# pena.net
KiCad netlist of a schematic drawn in EAGLE
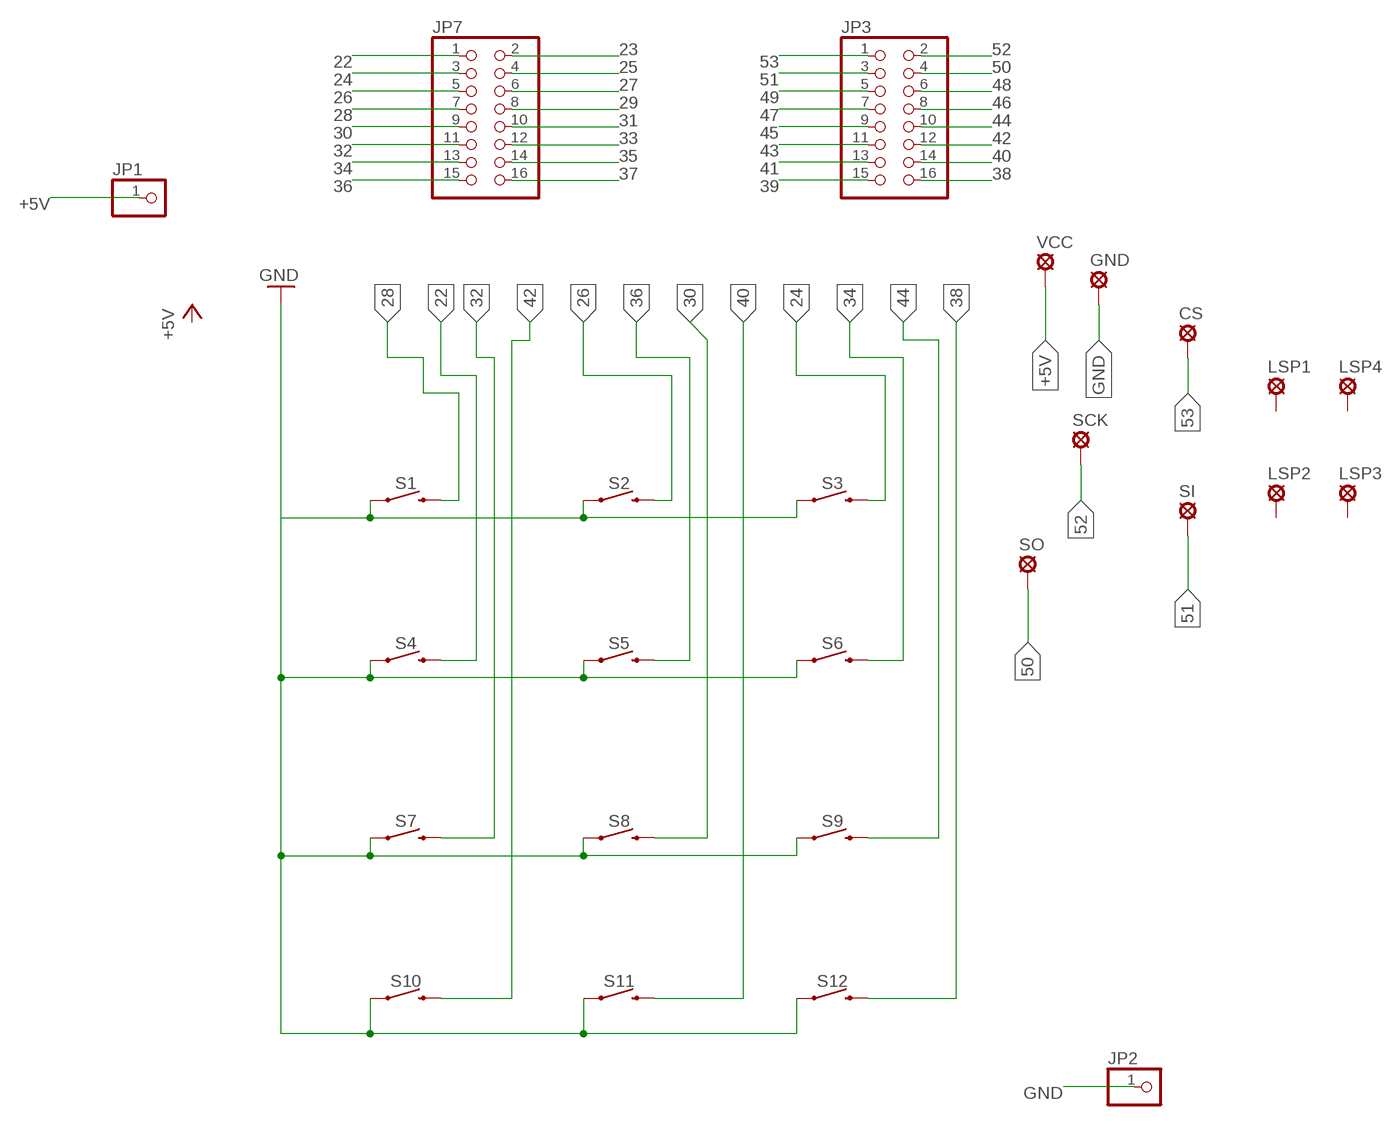
[diagram p0: schematic, sheet 1]

(export (version "E")
  (design (tool "Eeschema 10.0.6"))
  (components
    (comp (ref "CS")
      (value "SE11")
      (footprint "eagle-import:SE11")
      (libsource (lib "eagle-import") (part "SE11"))
    )
    (comp (ref "GND")
      (value "SE11")
      (footprint "eagle-import:SE11")
      (libsource (lib "eagle-import") (part "SE11"))
    )
    (comp (ref "JP1")
      (value "PINHD-1X1")
      (footprint "eagle-import:1X01")
      (libsource (lib "eagle-import") (part "PINHD-1X1"))
    )
    (comp (ref "JP2")
      (value "PINHD-1X1")
      (footprint "eagle-import:1X01")
      (libsource (lib "eagle-import") (part "PINHD-1X1"))
    )
    (comp (ref "JP3")
      (value "PINHD-2X8")
      (footprint "eagle-import:2X08")
      (libsource (lib "eagle-import") (part "PINHD-2X8"))
    )
    (comp (ref "JP7")
      (value "PINHD-2X8")
      (footprint "eagle-import:2X08")
      (libsource (lib "eagle-import") (part "PINHD-2X8"))
    )
    (comp (ref "LSP1")
      (value "SE11")
      (footprint "eagle-import:SE11")
      (libsource (lib "eagle-import") (part "SE11"))
    )
    (comp (ref "LSP2")
      (value "SE11")
      (footprint "eagle-import:SE11")
      (libsource (lib "eagle-import") (part "SE11"))
    )
    (comp (ref "LSP3")
      (value "SE11")
      (footprint "eagle-import:SE11")
      (libsource (lib "eagle-import") (part "SE11"))
    )
    (comp (ref "LSP4")
      (value "SE11")
      (footprint "eagle-import:SE11")
      (libsource (lib "eagle-import") (part "SE11"))
    )
    (comp (ref "S1")
      (value "MOMENTARY-SWITCH-SPST-PTH-12MM")
      (footprint "eagle-import:TACTILE_SWITCH_PTH_12MM")
      (libsource (lib "eagle-import") (part "MOMENTARY-SWITCH-SPST-PTH-12MM"))
    )
    (comp (ref "S2")
      (value "MOMENTARY-SWITCH-SPST-PTH-12MM")
      (footprint "eagle-import:TACTILE_SWITCH_PTH_12MM")
      (libsource (lib "eagle-import") (part "MOMENTARY-SWITCH-SPST-PTH-12MM"))
    )
    (comp (ref "S3")
      (value "MOMENTARY-SWITCH-SPST-PTH-12MM")
      (footprint "eagle-import:TACTILE_SWITCH_PTH_12MM")
      (libsource (lib "eagle-import") (part "MOMENTARY-SWITCH-SPST-PTH-12MM"))
    )
    (comp (ref "S4")
      (value "MOMENTARY-SWITCH-SPST-PTH-12MM")
      (footprint "eagle-import:TACTILE_SWITCH_PTH_12MM")
      (libsource (lib "eagle-import") (part "MOMENTARY-SWITCH-SPST-PTH-12MM"))
    )
    (comp (ref "S5")
      (value "MOMENTARY-SWITCH-SPST-PTH-12MM")
      (footprint "eagle-import:TACTILE_SWITCH_PTH_12MM")
      (libsource (lib "eagle-import") (part "MOMENTARY-SWITCH-SPST-PTH-12MM"))
    )
    (comp (ref "S6")
      (value "MOMENTARY-SWITCH-SPST-PTH-12MM")
      (footprint "eagle-import:TACTILE_SWITCH_PTH_12MM")
      (libsource (lib "eagle-import") (part "MOMENTARY-SWITCH-SPST-PTH-12MM"))
    )
    (comp (ref "S7")
      (value "MOMENTARY-SWITCH-SPST-PTH-12MM")
      (footprint "eagle-import:TACTILE_SWITCH_PTH_12MM")
      (libsource (lib "eagle-import") (part "MOMENTARY-SWITCH-SPST-PTH-12MM"))
    )
    (comp (ref "S8")
      (value "MOMENTARY-SWITCH-SPST-PTH-12MM")
      (footprint "eagle-import:TACTILE_SWITCH_PTH_12MM")
      (libsource (lib "eagle-import") (part "MOMENTARY-SWITCH-SPST-PTH-12MM"))
    )
    (comp (ref "S9")
      (value "MOMENTARY-SWITCH-SPST-PTH-12MM")
      (footprint "eagle-import:TACTILE_SWITCH_PTH_12MM")
      (libsource (lib "eagle-import") (part "MOMENTARY-SWITCH-SPST-PTH-12MM"))
    )
    (comp (ref "S10")
      (value "MOMENTARY-SWITCH-SPST-PTH-12MM")
      (footprint "eagle-import:TACTILE_SWITCH_PTH_12MM")
      (libsource (lib "eagle-import") (part "MOMENTARY-SWITCH-SPST-PTH-12MM"))
    )
    (comp (ref "S11")
      (value "MOMENTARY-SWITCH-SPST-PTH-12MM")
      (footprint "eagle-import:TACTILE_SWITCH_PTH_12MM")
      (libsource (lib "eagle-import") (part "MOMENTARY-SWITCH-SPST-PTH-12MM"))
    )
    (comp (ref "S12")
      (value "MOMENTARY-SWITCH-SPST-PTH-12MM")
      (footprint "eagle-import:TACTILE_SWITCH_PTH_12MM")
      (libsource (lib "eagle-import") (part "MOMENTARY-SWITCH-SPST-PTH-12MM"))
    )
    (comp (ref "SCK")
      (value "SE11")
      (footprint "eagle-import:SE11")
      (libsource (lib "eagle-import") (part "SE11"))
    )
    (comp (ref "SI")
      (value "SE11")
      (footprint "eagle-import:SE11")
      (libsource (lib "eagle-import") (part "SE11"))
    )
    (comp (ref "SO")
      (value "SE11")
      (footprint "eagle-import:SE11")
      (libsource (lib "eagle-import") (part "SE11"))
    )
    (comp (ref "VCC")
      (value "SE11")
      (footprint "eagle-import:SE11")
      (libsource (lib "eagle-import") (part "SE11"))
    )
  )
  (nets
    (net (code "1") (name "+5V") (class "Default")
      (node (ref "JP1") (pin "1") (pinfunction "1_1") (pintype "passive"))
      (node (ref "VCC") (pin "MP") (pinfunction "MP_MP") (pintype "passive"))
    )
    (net (code "2") (name "/23") (class "Default")
      (node (ref "JP7") (pin "2") (pinfunction "2_2") (pintype "passive"))
    )
    (net (code "3") (name "/25") (class "Default")
      (node (ref "JP7") (pin "4") (pinfunction "4_4") (pintype "passive"))
    )
    (net (code "4") (name "/27") (class "Default")
      (node (ref "JP7") (pin "6") (pinfunction "6_6") (pintype "passive"))
    )
    (net (code "5") (name "/29") (class "Default")
      (node (ref "JP7") (pin "8") (pinfunction "8_8") (pintype "passive"))
    )
    (net (code "6") (name "/31") (class "Default")
      (node (ref "JP7") (pin "10") (pinfunction "10_10") (pintype "passive"))
    )
    (net (code "7") (name "/33") (class "Default")
      (node (ref "JP7") (pin "12") (pinfunction "12_12") (pintype "passive"))
    )
    (net (code "8") (name "/35") (class "Default")
      (node (ref "JP7") (pin "14") (pinfunction "14_14") (pintype "passive"))
    )
    (net (code "9") (name "/37") (class "Default")
      (node (ref "JP7") (pin "16") (pinfunction "16_16") (pintype "passive"))
    )
    (net (code "10") (name "/39") (class "Default")
      (node (ref "JP3") (pin "15") (pinfunction "15_15") (pintype "passive"))
    )
    (net (code "11") (name "/41") (class "Default")
      (node (ref "JP3") (pin "13") (pinfunction "13_13") (pintype "passive"))
    )
    (net (code "12") (name "/43") (class "Default")
      (node (ref "JP3") (pin "11") (pinfunction "11_11") (pintype "passive"))
    )
    (net (code "13") (name "/45") (class "Default")
      (node (ref "JP3") (pin "9") (pinfunction "9_9") (pintype "passive"))
    )
    (net (code "14") (name "/46") (class "Default")
      (node (ref "JP3") (pin "8") (pinfunction "8_8") (pintype "passive"))
    )
    (net (code "15") (name "/47") (class "Default")
      (node (ref "JP3") (pin "7") (pinfunction "7_7") (pintype "passive"))
    )
    (net (code "16") (name "/48") (class "Default")
      (node (ref "JP3") (pin "6") (pinfunction "6_6") (pintype "passive"))
    )
    (net (code "17") (name "/49") (class "Default")
      (node (ref "JP3") (pin "5") (pinfunction "5_5") (pintype "passive"))
    )
    (net (code "18") (name "22") (class "Default")
      (node (ref "JP7") (pin "1") (pinfunction "1_1") (pintype "passive"))
      (node (ref "S4") (pin "3") (pinfunction "2_3") (pintype "passive"))
    )
    (net (code "19") (name "24") (class "Default")
      (node (ref "JP7") (pin "3") (pinfunction "3_3") (pintype "passive"))
      (node (ref "S3") (pin "3") (pinfunction "2_3") (pintype "passive"))
    )
    (net (code "20") (name "26") (class "Default")
      (node (ref "JP7") (pin "5") (pinfunction "5_5") (pintype "passive"))
      (node (ref "S2") (pin "3") (pinfunction "2_3") (pintype "passive"))
    )
    (net (code "21") (name "28") (class "Default")
      (node (ref "JP7") (pin "7") (pinfunction "7_7") (pintype "passive"))
      (node (ref "S1") (pin "3") (pinfunction "2_3") (pintype "passive"))
    )
    (net (code "22") (name "30") (class "Default")
      (node (ref "JP7") (pin "9") (pinfunction "9_9") (pintype "passive"))
      (node (ref "S8") (pin "3") (pinfunction "2_3") (pintype "passive"))
    )
    (net (code "23") (name "32") (class "Default")
      (node (ref "JP7") (pin "11") (pinfunction "11_11") (pintype "passive"))
      (node (ref "S7") (pin "3") (pinfunction "2_3") (pintype "passive"))
    )
    (net (code "24") (name "34") (class "Default")
      (node (ref "JP7") (pin "13") (pinfunction "13_13") (pintype "passive"))
      (node (ref "S6") (pin "3") (pinfunction "2_3") (pintype "passive"))
    )
    (net (code "25") (name "36") (class "Default")
      (node (ref "JP7") (pin "15") (pinfunction "15_15") (pintype "passive"))
      (node (ref "S5") (pin "3") (pinfunction "2_3") (pintype "passive"))
    )
    (net (code "26") (name "38") (class "Default")
      (node (ref "JP3") (pin "16") (pinfunction "16_16") (pintype "passive"))
      (node (ref "S12") (pin "3") (pinfunction "2_3") (pintype "passive"))
    )
    (net (code "27") (name "40") (class "Default")
      (node (ref "JP3") (pin "14") (pinfunction "14_14") (pintype "passive"))
      (node (ref "S11") (pin "3") (pinfunction "2_3") (pintype "passive"))
    )
    (net (code "28") (name "42") (class "Default")
      (node (ref "JP3") (pin "12") (pinfunction "12_12") (pintype "passive"))
      (node (ref "S10") (pin "3") (pinfunction "2_3") (pintype "passive"))
    )
    (net (code "29") (name "44") (class "Default")
      (node (ref "JP3") (pin "10") (pinfunction "10_10") (pintype "passive"))
      (node (ref "S9") (pin "3") (pinfunction "2_3") (pintype "passive"))
    )
    (net (code "30") (name "50") (class "Default")
      (node (ref "JP3") (pin "4") (pinfunction "4_4") (pintype "passive"))
      (node (ref "SO") (pin "MP") (pinfunction "MP_MP") (pintype "passive"))
    )
    (net (code "31") (name "51") (class "Default")
      (node (ref "JP3") (pin "3") (pinfunction "3_3") (pintype "passive"))
      (node (ref "SI") (pin "MP") (pinfunction "MP_MP") (pintype "passive"))
    )
    (net (code "32") (name "52") (class "Default")
      (node (ref "JP3") (pin "2") (pinfunction "2_2") (pintype "passive"))
      (node (ref "SCK") (pin "MP") (pinfunction "MP_MP") (pintype "passive"))
    )
    (net (code "33") (name "53") (class "Default")
      (node (ref "CS") (pin "MP") (pinfunction "MP_MP") (pintype "passive"))
      (node (ref "JP3") (pin "1") (pinfunction "1_1") (pintype "passive"))
    )
    (net (code "34") (name "GND") (class "Default")
      (node (ref "GND") (pin "MP") (pinfunction "MP_MP") (pintype "passive"))
      (node (ref "JP2") (pin "1") (pinfunction "1_1") (pintype "passive"))
      (node (ref "S1") (pin "1") (pinfunction "1_1") (pintype "passive"))
      (node (ref "S10") (pin "1") (pinfunction "1_1") (pintype "passive"))
      (node (ref "S11") (pin "1") (pinfunction "1_1") (pintype "passive"))
      (node (ref "S12") (pin "1") (pinfunction "1_1") (pintype "passive"))
      (node (ref "S2") (pin "1") (pinfunction "1_1") (pintype "passive"))
      (node (ref "S3") (pin "1") (pinfunction "1_1") (pintype "passive"))
      (node (ref "S4") (pin "1") (pinfunction "1_1") (pintype "passive"))
      (node (ref "S5") (pin "1") (pinfunction "1_1") (pintype "passive"))
      (node (ref "S6") (pin "1") (pinfunction "1_1") (pintype "passive"))
      (node (ref "S7") (pin "1") (pinfunction "1_1") (pintype "passive"))
      (node (ref "S8") (pin "1") (pinfunction "1_1") (pintype "passive"))
      (node (ref "S9") (pin "1") (pinfunction "1_1") (pintype "passive"))
    )
    (net (code "35") (name "unconnected-(LSP1-PadMP)") (class "Default")
      (node (ref "LSP1") (pin "MP") (pinfunction "MP_MP") (pintype "passive"))
    )
    (net (code "36") (name "unconnected-(LSP2-PadMP)") (class "Default")
      (node (ref "LSP2") (pin "MP") (pinfunction "MP_MP") (pintype "passive"))
    )
    (net (code "37") (name "unconnected-(LSP3-PadMP)") (class "Default")
      (node (ref "LSP3") (pin "MP") (pinfunction "MP_MP") (pintype "passive"))
    )
    (net (code "38") (name "unconnected-(LSP4-PadMP)") (class "Default")
      (node (ref "LSP4") (pin "MP") (pinfunction "MP_MP") (pintype "passive"))
    )
  )
)
